# RF.net
KiCad netlist of a schematic drawn in Altium Designer
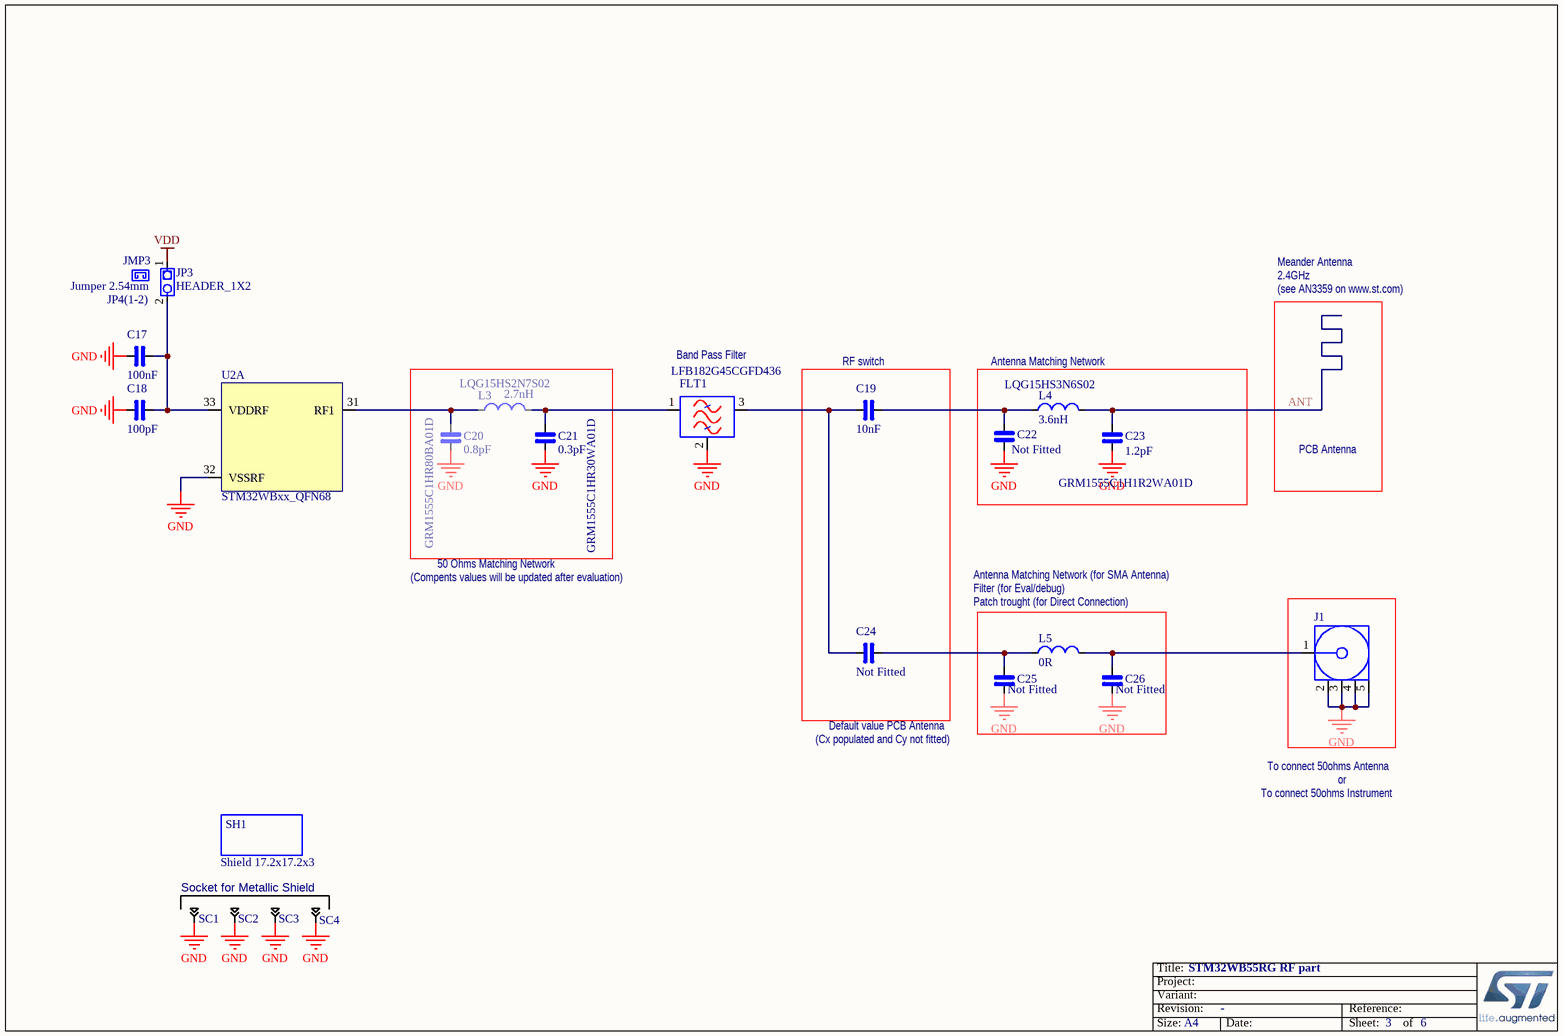
[diagram p0: RF.SchDoc]

(export (version "E")
  (design (tool "Eeschema 10.0.6"))
  (components
    (comp (ref "C17")
      (value "100nF")
      (footprint "0603_CAP_NPOL")
      (description "Capacitor_not polarized")
      (libsource (lib "ST_Lib3D") (part "CAP_NPOL"))
    )
    (comp (ref "C18")
      (value "100pF")
      (footprint "0603_CAP_NPOL")
      (description "Capacitor_not polarized")
      (libsource (lib "ST_Lib3D") (part "CAP_NPOL"))
    )
    (comp (ref "C19")
      (value "10nF")
      (footprint "0603_CAP_NPOL")
      (description "Capacitor_not polarized")
      (libsource (lib "ST_Lib3D") (part "CAP_NPOL"))
    )
    (comp (ref "C20")
      (value "0.8pF")
      (footprint "0603_CAP_NPOL")
      (description "Capacitor_not polarized")
      (fields (field (name "REF") "GRM1555C1HR80BA01D"))
      (libsource (lib "Passive") (part "CAP_NPOL"))
    )
    (comp (ref "C21")
      (value "0.3pF")
      (footprint "0603_CAP_NPOL")
      (description "Capacitor_not polarized")
      (fields (field (name "REF") "GRM1555C1HR30WA01D"))
      (libsource (lib "Passive") (part "CAP_NPOL"))
    )
    (comp (ref "C22")
      (value "~")
      (footprint "0603_CAP_NPOL")
      (description "Capacitor_not polarized")
      (fields (field (name "FITTED") "Not Fitted"))
      (libsource (lib "ST_Lib3D") (part "CAP_NPOL"))
    )
    (comp (ref "C23")
      (value "1.2pF")
      (footprint "0603_CAP_NPOL")
      (description "Capacitor_not polarized")
      (fields (field (name "REF") "GRM1555C1H1R2WA01D"))
      (libsource (lib "ST_Lib3D") (part "CAP_NPOL"))
    )
    (comp (ref "C24")
      (value "~")
      (footprint "0603_CAP_NPOL")
      (description "Capacitor_not polarized")
      (fields (field (name "FITTED") "Not Fitted"))
      (libsource (lib "ST_Lib3D") (part "CAP_NPOL"))
    )
    (comp (ref "C25")
      (value "~")
      (footprint "0603_CAP_NPOL")
      (description "Capacitor_not polarized")
      (fields (field (name "FITTED") "Not Fitted"))
      (libsource (lib "ST_Lib3D") (part "CAP_NPOL"))
    )
    (comp (ref "C26")
      (value "~")
      (footprint "0603_CAP_NPOL")
      (description "Capacitor_not polarized")
      (fields (field (name "FITTED") "Not Fitted"))
      (libsource (lib "ST_Lib3D") (part "CAP_NPOL"))
    )
    (comp (ref "FLT1")
      (value "LFB182G45CGFD436")
      (footprint "LFB182G45CGFD436")
      (description "Band Pass Filter Murata LFB182G45CGFD436")
      (libsource (lib "Passive") (part "LFB182G45CGFD436"))
    )
    (comp (ref "J1")
      (value "731000114")
      (footprint "MOLX-731000114_V")
      (description "SMA Right-Angle PCB Jack Receptacle, Brass Body, Gold Plated, 50 Ohm, 5-Pin THD, RoHS, Tray")
      (fields (field (name "MANUFACTURER") "Molex"))
      (libsource (lib "Altium Content Vault") (part "CN-S-4F-RF5"))
    )
    (comp (ref "JMP3")
      (value "Jumper 2.54mm")
      (footprint "Jumper 2.54mm BLACK")
      (fields (field (name "DEFAULT") "JP4(1-2)"))
      (libsource (lib "Connector") (part "Jumper 2.54mm"))
    )
    (comp (ref "JP3")
      (value "HEADER_1X2")
      (footprint "GP_2x1_2mm")
      (libsource (lib "Connector") (part "HEADER_1X2_L"))
    )
    (comp (ref "L3")
      (value "2.7nH")
      (footprint "0402_COIL")
      (fields (field (name "REF") "LQG15HS2N7S02"))
      (libsource (lib "Passive") (part "INDUCTOR_SMD_STDL"))
    )
    (comp (ref "L4")
      (value "3.6nH")
      (footprint "0402_COIL")
      (fields (field (name "REF") "LQG15HS3N6S02"))
      (libsource (lib "Passive") (part "INDUCTOR_SMD_STDL"))
    )
    (comp (ref "L5")
      (value "0R")
      (footprint "0402_COIL")
      (libsource (lib "Passive") (part "INDUCTOR_SMD_STDL"))
    )
    (comp (ref "SC1")
      (value "Shield Clip_A 3.9x1.1x1.28")
      (footprint "Shield Clip_A 3.9x1.1x1.28")
      (description "Harwin S0951-46R")
      (libsource (lib "Box_Meca") (part "Shield Clip_A 3.9x1.1x1.28"))
    )
    (comp (ref "SC2")
      (value "Shield Clip_A 3.9x1.1x1.28")
      (footprint "Shield Clip_A 3.9x1.1x1.28")
      (description "Harwin S0951-46R")
      (libsource (lib "Box_Meca") (part "Shield Clip_A 3.9x1.1x1.28"))
    )
    (comp (ref "SC3")
      (value "Shield Clip_A 3.9x1.1x1.28")
      (footprint "Shield Clip_A 3.9x1.1x1.28")
      (description "Harwin S0951-46R")
      (libsource (lib "Box_Meca") (part "Shield Clip_A 3.9x1.1x1.28"))
    )
    (comp (ref "SC4")
      (value "Shield Clip_A 3.9x1.1x1.28")
      (footprint "Shield Clip_A 3.9x1.1x1.28")
      (description "Harwin S0951-46R")
      (libsource (lib "Box_Meca") (part "Shield Clip_A 3.9x1.1x1.28"))
    )
    (comp (ref "SH1")
      (value "Shield 17.2x17.2x3")
      (footprint "Shield 17.2x17.2x3")
      (description "Shield")
      (libsource (lib "Box_Meca") (part "Shield"))
    )
    (comp (ref "U2")
      (value "STM32WBxx_QFN68")
      (footprint "VFQFPN68_8x8x0.1_p0.4")
      (libsource (lib "Active") (part "STM32WBxx_QFN68"))
    )
  )
  (nets
    (net (code "1") (name "/ANT") (class "Default")
      (node (ref "C23") (pin "2") (pinfunction "2_2") (pintype "passive"))
      (node (ref "L4") (pin "2") (pinfunction "2_2") (pintype "passive"))
    )
    (net (code "2") (name "GND") (class "Default")
      (node (ref "C17") (pin "1") (pinfunction "1_1") (pintype "passive"))
      (node (ref "C18") (pin "1") (pinfunction "1_1") (pintype "passive"))
      (node (ref "C20") (pin "1") (pinfunction "1_1") (pintype "passive"))
      (node (ref "C21") (pin "1") (pinfunction "1_1") (pintype "passive"))
      (node (ref "C22") (pin "2") (pinfunction "2_2") (pintype "passive"))
      (node (ref "C23") (pin "1") (pinfunction "1_1") (pintype "passive"))
      (node (ref "C25") (pin "1") (pinfunction "1_1") (pintype "passive"))
      (node (ref "C26") (pin "1") (pinfunction "1_1") (pintype "passive"))
      (node (ref "FLT1") (pin "2") (pinfunction "GND_2") (pintype "passive"))
      (node (ref "J1") (pin "2") (pinfunction "2_2") (pintype "passive"))
      (node (ref "J1") (pin "3") (pinfunction "3_3") (pintype "passive"))
      (node (ref "J1") (pin "4") (pinfunction "4_4") (pintype "passive"))
      (node (ref "J1") (pin "5") (pinfunction "5_5") (pintype "passive"))
      (node (ref "SC1") (pin "1") (pinfunction "1_1") (pintype "passive"))
      (node (ref "SC2") (pin "1") (pinfunction "1_1") (pintype "passive"))
      (node (ref "SC3") (pin "1") (pinfunction "1_1") (pintype "passive"))
      (node (ref "SC4") (pin "1") (pinfunction "1_1") (pintype "passive"))
      (node (ref "U2") (pin "32") (pinfunction "VSSRF_32") (pintype "passive"))
    )
    (net (code "3") (name "Net-(C19-Pad1)") (class "Default")
      (node (ref "C19") (pin "1") (pinfunction "1_1") (pintype "passive"))
      (node (ref "C24") (pin "1") (pinfunction "1_1") (pintype "passive"))
      (node (ref "FLT1") (pin "3") (pinfunction "I/O_3") (pintype "passive"))
    )
    (net (code "4") (name "Net-(C19-Pad2)") (class "Default")
      (node (ref "C19") (pin "2") (pinfunction "2_2") (pintype "passive"))
      (node (ref "C22") (pin "1") (pinfunction "1_1") (pintype "passive"))
      (node (ref "L4") (pin "1") (pinfunction "1_1") (pintype "passive"))
    )
    (net (code "5") (name "Net-(C21-Pad2)") (class "Default")
      (node (ref "C21") (pin "2") (pinfunction "2_2") (pintype "passive"))
      (node (ref "FLT1") (pin "1") (pinfunction "I/O_1") (pintype "passive"))
      (node (ref "L3") (pin "2") (pinfunction "2_2") (pintype "passive"))
    )
    (net (code "6") (name "Net-(C24-Pad2)") (class "Default")
      (node (ref "C24") (pin "2") (pinfunction "2_2") (pintype "passive"))
      (node (ref "C25") (pin "2") (pinfunction "2_2") (pintype "passive"))
      (node (ref "L5") (pin "1") (pinfunction "1_1") (pintype "passive"))
    )
    (net (code "7") (name "Net-(C26-Pad2)") (class "Default")
      (node (ref "C26") (pin "2") (pinfunction "2_2") (pintype "passive"))
      (node (ref "J1") (pin "1") (pinfunction "1_1") (pintype "passive"))
      (node (ref "L5") (pin "2") (pinfunction "2_2") (pintype "passive"))
    )
    (net (code "8") (name "Net-(U2A-RF1)") (class "Default")
      (node (ref "C20") (pin "2") (pinfunction "2_2") (pintype "passive"))
      (node (ref "L3") (pin "1") (pinfunction "1_1") (pintype "passive"))
      (node (ref "U2") (pin "31") (pinfunction "RF1_31") (pintype "passive"))
    )
    (net (code "9") (name "Net-(U2A-VDDRF)") (class "Default")
      (node (ref "C17") (pin "2") (pinfunction "2_2") (pintype "passive"))
      (node (ref "C18") (pin "2") (pinfunction "2_2") (pintype "passive"))
      (node (ref "JP3") (pin "2") (pinfunction "2_2") (pintype "passive"))
      (node (ref "U2") (pin "33") (pinfunction "VDDRF_33") (pintype "passive"))
    )
    (net (code "10") (name "VDD") (class "Default")
      (node (ref "JP3") (pin "1") (pinfunction "1_1") (pintype "passive"))
    )
  )
)
